# 1_1.net
KiCad netlist of a schematic drawn in EAGLE
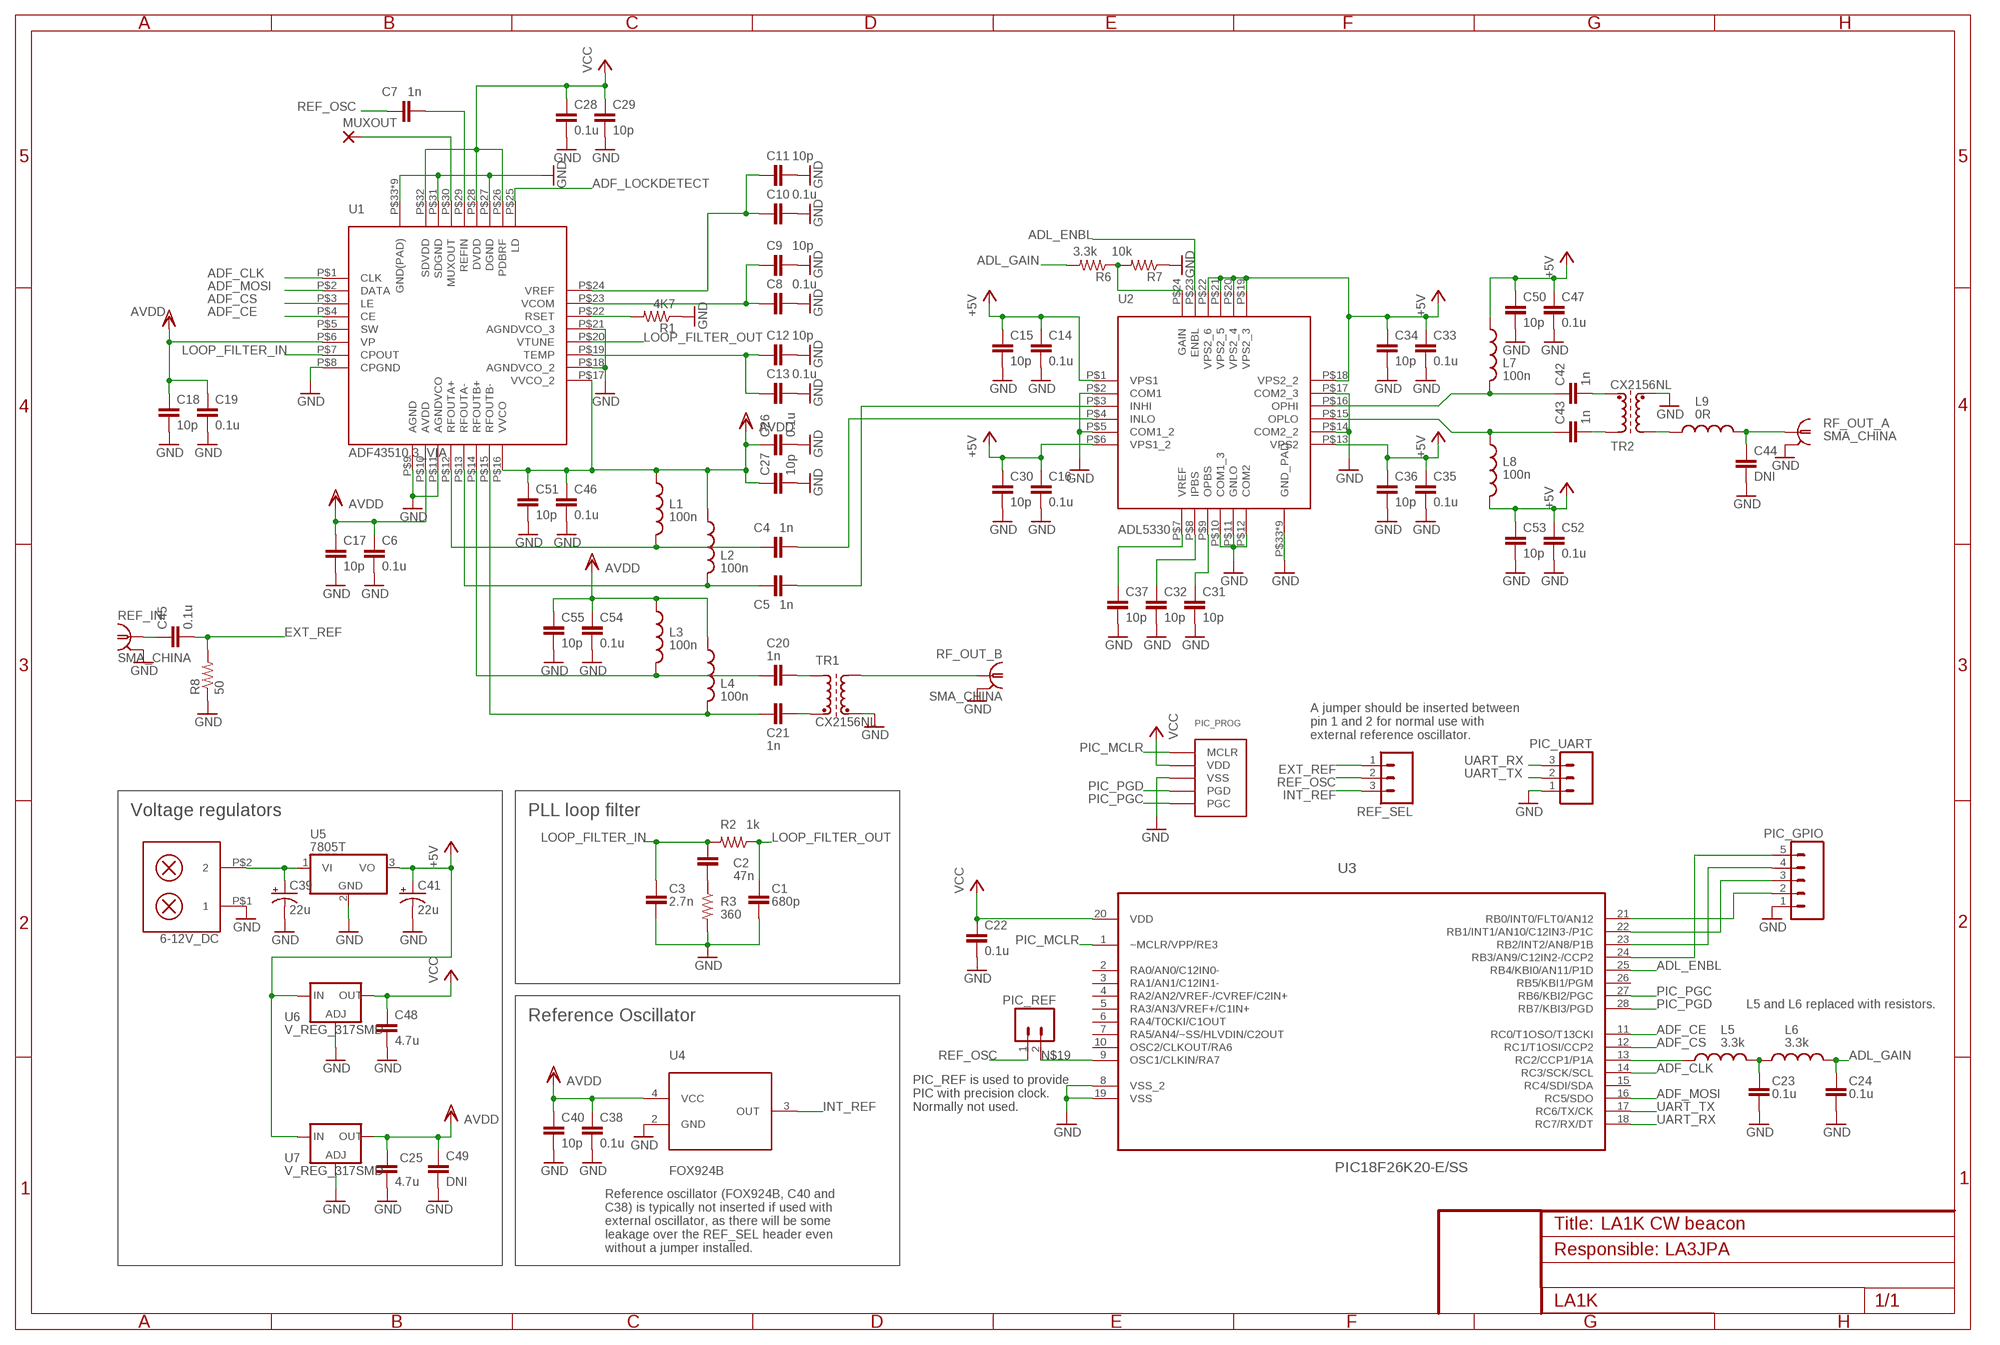
[diagram p0: schematic, sheet 1]

(export (version "E")
  (design (tool "Eeschema 10.0.6"))
  (components
    (comp (ref "6-12V_DC")
      (value "PK5602")
      (footprint "eagle-import:PK5602")
      (fields (field (name "PARTNO") "1984617"))
      (libsource (lib "eagle-import") (part "PK5602"))
    )
    (comp (ref "C1")
      (value "680p")
      (footprint "eagle-import:0603-CAP")
      (fields (field (name "PARTNO") "GRM1885C1H681JA01D"))
      (libsource (lib "eagle-import") (part "CAP0603-CAP"))
    )
    (comp (ref "C2")
      (value "47n")
      (footprint "eagle-import:0603-CAP")
      (fields (field (name "PARTNO") "GRM188R71E473JA01D"))
      (libsource (lib "eagle-import") (part "CAP0603-CAP"))
    )
    (comp (ref "C3")
      (value "2.7n")
      (footprint "eagle-import:0603-CAP")
      (fields (field (name "PARTNO") "GRM1885C1H272JA01D"))
      (libsource (lib "eagle-import") (part "CAP0603-CAP"))
    )
    (comp (ref "C4")
      (value "1n")
      (footprint "eagle-import:0603-CAP")
      (fields (field (name "PARTNO") "GRM1885C1H102FA01D"))
      (libsource (lib "eagle-import") (part "CAP0603-CAP"))
    )
    (comp (ref "C5")
      (value "1n")
      (footprint "eagle-import:0603-CAP")
      (fields (field (name "PARTNO") "GRM1885C1H102FA01D"))
      (libsource (lib "eagle-import") (part "CAP0603-CAP"))
    )
    (comp (ref "C6")
      (value "0.1u")
      (footprint "eagle-import:0603-CAP")
      (fields (field (name "PARTNO") "GRM188R71E104KA01D"))
      (libsource (lib "eagle-import") (part "CAP0603-CAP"))
    )
    (comp (ref "C7")
      (value "1n")
      (footprint "eagle-import:0603-CAP")
      (fields (field (name "PARTNO") "GRM1885C1H102FA01D"))
      (libsource (lib "eagle-import") (part "CAP0603-CAP"))
    )
    (comp (ref "C8")
      (value "0.1u")
      (footprint "eagle-import:0603-CAP")
      (fields (field (name "PARTNO") "GRM188R71E104KA01D"))
      (libsource (lib "eagle-import") (part "CAP0603-CAP"))
    )
    (comp (ref "C9")
      (value "10p")
      (footprint "eagle-import:0603-CAP")
      (fields (field (name "PARTNO") "GRM1885C1H100FA01D"))
      (libsource (lib "eagle-import") (part "CAP0603-CAP"))
    )
    (comp (ref "C10")
      (value "0.1u")
      (footprint "eagle-import:0603-CAP")
      (fields (field (name "PARTNO") "GRM188R71E104KA01D"))
      (libsource (lib "eagle-import") (part "CAP0603-CAP"))
    )
    (comp (ref "C11")
      (value "10p")
      (footprint "eagle-import:0603-CAP")
      (fields (field (name "PARTNO") "GRM1885C1H100FA01D"))
      (libsource (lib "eagle-import") (part "CAP0603-CAP"))
    )
    (comp (ref "C12")
      (value "10p")
      (footprint "eagle-import:0603-CAP")
      (fields (field (name "PARTNO") "GRM1885C1H100FA01D"))
      (libsource (lib "eagle-import") (part "CAP0603-CAP"))
    )
    (comp (ref "C13")
      (value "0.1u")
      (footprint "eagle-import:0603-CAP")
      (fields (field (name "PARTNO") "GRM188R71E104KA01D"))
      (libsource (lib "eagle-import") (part "CAP0603-CAP"))
    )
    (comp (ref "C14")
      (value "0.1u")
      (footprint "eagle-import:0603-CAP")
      (fields (field (name "PARTNO") "GRM188R71E104KA01D"))
      (libsource (lib "eagle-import") (part "CAP0603-CAP"))
    )
    (comp (ref "C15")
      (value "10p")
      (footprint "eagle-import:0603-CAP")
      (fields (field (name "PARTNO") "GRM1885C1H100FA01D"))
      (libsource (lib "eagle-import") (part "CAP0603-CAP"))
    )
    (comp (ref "C16")
      (value "0.1u")
      (footprint "eagle-import:0603-CAP")
      (fields (field (name "PARTNO") "GRM188R71E104KA01D"))
      (libsource (lib "eagle-import") (part "CAP0603-CAP"))
    )
    (comp (ref "C17")
      (value "10p")
      (footprint "eagle-import:0603-CAP")
      (fields (field (name "PARTNO") "GRM1885C1H100FA01D"))
      (libsource (lib "eagle-import") (part "CAP0603-CAP"))
    )
    (comp (ref "C18")
      (value "10p")
      (footprint "eagle-import:0603-CAP")
      (fields (field (name "PARTNO") "GRM1885C1H100FA01D"))
      (libsource (lib "eagle-import") (part "CAP0603-CAP"))
    )
    (comp (ref "C19")
      (value "0.1u")
      (footprint "eagle-import:0603-CAP")
      (fields (field (name "PARTNO") "GRM188R71E104KA01D"))
      (libsource (lib "eagle-import") (part "CAP0603-CAP"))
    )
    (comp (ref "C20")
      (value "1n")
      (footprint "eagle-import:0603-CAP")
      (fields (field (name "PARTNO") "GRM1885C1H102FA01D"))
      (libsource (lib "eagle-import") (part "CAP0603-CAP"))
    )
    (comp (ref "C21")
      (value "1n")
      (footprint "eagle-import:0603-CAP")
      (fields (field (name "PARTNO") "GRM1885C1H102FA01D"))
      (libsource (lib "eagle-import") (part "CAP0603-CAP"))
    )
    (comp (ref "C22")
      (value "0.1u")
      (footprint "eagle-import:0603-CAP")
      (fields (field (name "PARTNO") "GRM188R71E104KA01D"))
      (libsource (lib "eagle-import") (part "CAP0603-CAP"))
    )
    (comp (ref "C23")
      (value "0.1u")
      (footprint "eagle-import:0603-CAP")
      (fields (field (name "PARTNO") "GRM188R71E104KA01D"))
      (libsource (lib "eagle-import") (part "CAP0603-CAP"))
    )
    (comp (ref "C24")
      (value "0.1u")
      (footprint "eagle-import:0603-CAP")
      (fields (field (name "PARTNO") "GRM188R71E104KA01D"))
      (libsource (lib "eagle-import") (part "CAP0603-CAP"))
    )
    (comp (ref "C25")
      (value "4.7u")
      (footprint "eagle-import:C0805")
      (fields (field (name "PARTNO") "GRM21BR61E475KA12K"))
      (libsource (lib "eagle-import") (part "C-EUC0805"))
    )
    (comp (ref "C26")
      (value "0.1u")
      (footprint "eagle-import:0603-CAP")
      (fields (field (name "PARTNO") "GRM188R71E104KA01D"))
      (libsource (lib "eagle-import") (part "CAP0603-CAP"))
    )
    (comp (ref "C27")
      (value "10p")
      (footprint "eagle-import:0603-CAP")
      (fields (field (name "PARTNO") "GRM1885C1H100FA01D"))
      (libsource (lib "eagle-import") (part "CAP0603-CAP"))
    )
    (comp (ref "C28")
      (value "0.1u")
      (footprint "eagle-import:0603-CAP")
      (fields (field (name "PARTNO") "GRM188R71E104KA01D"))
      (libsource (lib "eagle-import") (part "CAP0603-CAP"))
    )
    (comp (ref "C29")
      (value "10p")
      (footprint "eagle-import:0603-CAP")
      (fields (field (name "PARTNO") "GRM1885C1H100FA01D"))
      (libsource (lib "eagle-import") (part "CAP0603-CAP"))
    )
    (comp (ref "C30")
      (value "10p")
      (footprint "eagle-import:0603-CAP")
      (fields (field (name "PARTNO") "GRM1885C1H100FA01D"))
      (libsource (lib "eagle-import") (part "CAP0603-CAP"))
    )
    (comp (ref "C31")
      (value "10p")
      (footprint "eagle-import:0603-CAP")
      (fields (field (name "PARTNO") "GRM1885C1H100FA01D"))
      (libsource (lib "eagle-import") (part "CAP0603-CAP"))
    )
    (comp (ref "C32")
      (value "10p")
      (footprint "eagle-import:0603-CAP")
      (fields (field (name "PARTNO") "GRM1885C1H100FA01D"))
      (libsource (lib "eagle-import") (part "CAP0603-CAP"))
    )
    (comp (ref "C33")
      (value "0.1u")
      (footprint "eagle-import:0603-CAP")
      (fields (field (name "PARTNO") "GRM188R71E104KA01D"))
      (libsource (lib "eagle-import") (part "CAP0603-CAP"))
    )
    (comp (ref "C34")
      (value "10p")
      (footprint "eagle-import:0603-CAP")
      (fields (field (name "PARTNO") "GRM1885C1H100FA01D"))
      (libsource (lib "eagle-import") (part "CAP0603-CAP"))
    )
    (comp (ref "C35")
      (value "0.1u")
      (footprint "eagle-import:0603-CAP")
      (fields (field (name "PARTNO") "GRM188R71E104KA01D"))
      (libsource (lib "eagle-import") (part "CAP0603-CAP"))
    )
    (comp (ref "C36")
      (value "10p")
      (footprint "eagle-import:0603-CAP")
      (fields (field (name "PARTNO") "GRM1885C1H100FA01D"))
      (libsource (lib "eagle-import") (part "CAP0603-CAP"))
    )
    (comp (ref "C37")
      (value "10p")
      (footprint "eagle-import:0603-CAP")
      (fields (field (name "PARTNO") "GRM1885C1H100FA01D"))
      (libsource (lib "eagle-import") (part "CAP0603-CAP"))
    )
    (comp (ref "C38")
      (value "0.1u")
      (footprint "eagle-import:0603-CAP")
      (fields (field (name "PARTNO") "GRM188R71E104KA01D"))
      (libsource (lib "eagle-import") (part "CAP0603-CAP"))
    )
    (comp (ref "C39")
      (value "22u")
      (footprint "eagle-import:VISHAY_C")
      (fields (field (name "PARTNO") "TH4C226K016C1400"))
      (libsource (lib "eagle-import") (part "CAP_POLSMD"))
    )
    (comp (ref "C40")
      (value "10p")
      (footprint "eagle-import:0603-CAP")
      (fields (field (name "PARTNO") "GRM1885C1H100FA01D"))
      (libsource (lib "eagle-import") (part "CAP0603-CAP"))
    )
    (comp (ref "C41")
      (value "22u")
      (footprint "eagle-import:VISHAY_C")
      (fields (field (name "PARTNO") "TH4C226K016C1400"))
      (libsource (lib "eagle-import") (part "CAP_POLSMD"))
    )
    (comp (ref "C42")
      (value "1n")
      (footprint "eagle-import:C0805K")
      (fields (field (name "PARTNO") "GRM1885C1H102FA01D"))
      (libsource (lib "eagle-import") (part "CAP"))
    )
    (comp (ref "C43")
      (value "1n")
      (footprint "eagle-import:C0805K")
      (fields (field (name "PARTNO") "GRM1885C1H102FA01D"))
      (libsource (lib "eagle-import") (part "CAP"))
    )
    (comp (ref "C44")
      (value "DNI")
      (footprint "eagle-import:C0805K")
      (libsource (lib "eagle-import") (part "CAP"))
    )
    (comp (ref "C45")
      (value "0.1u")
      (footprint "eagle-import:0603-CAP")
      (fields (field (name "PARTNO") "GRM188R71E104KA01D"))
      (libsource (lib "eagle-import") (part "CAP0603-CAP"))
    )
    (comp (ref "C46")
      (value "0.1u")
      (footprint "eagle-import:0603-CAP")
      (fields (field (name "PARTNO") "GRM188R71E104KA01D"))
      (libsource (lib "eagle-import") (part "CAP0603-CAP"))
    )
    (comp (ref "C47")
      (value "0.1u")
      (footprint "eagle-import:0603-CAP")
      (fields (field (name "PARTNO") "GRM188R71E104KA01D"))
      (libsource (lib "eagle-import") (part "CAP0603-CAP"))
    )
    (comp (ref "C48")
      (value "4.7u")
      (footprint "eagle-import:C0805")
      (fields (field (name "PARTNO") "GRM21BR61E475KA12K"))
      (libsource (lib "eagle-import") (part "C-EUC0805"))
    )
    (comp (ref "C49")
      (value "DNI")
      (footprint "eagle-import:C0805")
      (libsource (lib "eagle-import") (part "C-EUC0805"))
    )
    (comp (ref "C50")
      (value "10p")
      (footprint "eagle-import:0603-CAP")
      (fields (field (name "PARTNO") "GRM1885C1H100FA01D"))
      (libsource (lib "eagle-import") (part "CAP0603-CAP"))
    )
    (comp (ref "C51")
      (value "10p")
      (footprint "eagle-import:0603-CAP")
      (fields (field (name "PARTNO") "GRM1885C1H100FA01D"))
      (libsource (lib "eagle-import") (part "CAP0603-CAP"))
    )
    (comp (ref "C52")
      (value "0.1u")
      (footprint "eagle-import:0603-CAP")
      (fields (field (name "PARTNO") "GRM188R71E104KA01D"))
      (libsource (lib "eagle-import") (part "CAP0603-CAP"))
    )
    (comp (ref "C53")
      (value "10p")
      (footprint "eagle-import:0603-CAP")
      (fields (field (name "PARTNO") "GRM1885C1H100FA01D"))
      (libsource (lib "eagle-import") (part "CAP0603-CAP"))
    )
    (comp (ref "C54")
      (value "0.1u")
      (footprint "eagle-import:0603-CAP")
      (fields (field (name "PARTNO") "GRM188R71E104KA01D"))
      (libsource (lib "eagle-import") (part "CAP0603-CAP"))
    )
    (comp (ref "C55")
      (value "10p")
      (footprint "eagle-import:0603-CAP")
      (fields (field (name "PARTNO") "GRM1885C1H100FA01D"))
      (libsource (lib "eagle-import") (part "CAP0603-CAP"))
    )
    (comp (ref "L1")
      (value "100n")
      (footprint "eagle-import:0603")
      (fields (field (name "PARTNO") "LQW18ANR10J00D"))
      (libsource (lib "eagle-import") (part "INDUCTOR0603"))
    )
    (comp (ref "L2")
      (value "100n")
      (footprint "eagle-import:0603")
      (fields (field (name "PARTNO") "LQW18ANR10J00D"))
      (libsource (lib "eagle-import") (part "INDUCTOR0603"))
    )
    (comp (ref "L3")
      (value "100n")
      (footprint "eagle-import:0603")
      (fields (field (name "PARTNO") "LQW18ANR10J00D"))
      (libsource (lib "eagle-import") (part "INDUCTOR0603"))
    )
    (comp (ref "L4")
      (value "100n")
      (footprint "eagle-import:0603")
      (fields (field (name "PARTNO") "LQW18ANR10J00D"))
      (libsource (lib "eagle-import") (part "INDUCTOR0603"))
    )
    (comp (ref "L5")
      (value "3.3k")
      (footprint "eagle-import:0603")
      (fields (field (name "PARTNO") "MCR03ERTF3321"))
      (libsource (lib "eagle-import") (part "INDUCTOR0603"))
    )
    (comp (ref "L6")
      (value "3.3k")
      (footprint "eagle-import:0603")
      (fields (field (name "PARTNO") "MCR03ERTF3321"))
      (libsource (lib "eagle-import") (part "INDUCTOR0603"))
    )
    (comp (ref "L7")
      (value "100n")
      (footprint "eagle-import:C0805K")
      (fields (field (name "PARTNO") "LQW18ANR10J00D"))
      (libsource (lib "eagle-import") (part "INDUCTOR"))
    )
    (comp (ref "L8")
      (value "100n")
      (footprint "eagle-import:C0805K")
      (fields (field (name "PARTNO") "LQW18ANR10J00D"))
      (libsource (lib "eagle-import") (part "INDUCTOR"))
    )
    (comp (ref "L9")
      (value "0R")
      (footprint "eagle-import:C0805K")
      (libsource (lib "eagle-import") (part "INDUCTOR"))
    )
    (comp (ref "MUXOUT")
      (value "SMD2")
      (footprint "eagle-import:SMD1,27-2,54")
      (libsource (lib "eagle-import") (part "SMD2"))
    )
    (comp (ref "PIC_GPIO")
      (value "M05PTH")
      (footprint "eagle-import:1X05")
      (libsource (lib "eagle-import") (part "M05PTH"))
    )
    (comp (ref "PIC_PROG")
      (value "1X5_ICSP")
      (footprint "eagle-import:1X5_2MM")
      (fields (field (name "PARTNO") "M22-2510505"))
      (libsource (lib "eagle-import") (part "1X5_ICSP"))
    )
    (comp (ref "PIC_REF")
      (value "M02PTH")
      (footprint "eagle-import:1X02")
      (libsource (lib "eagle-import") (part "M02PTH"))
    )
    (comp (ref "PIC_UART")
      (value "M03PTH")
      (footprint "eagle-import:1X03")
      (libsource (lib "eagle-import") (part "M03PTH"))
    )
    (comp (ref "R1")
      (value "4K7")
      (footprint "eagle-import:0603-RES")
      (fields (field (name "PARTNO") "MCR03ERTF4701"))
      (libsource (lib "eagle-import") (part "RESISTOR0603-RES"))
    )
    (comp (ref "R2")
      (value "1k")
      (footprint "eagle-import:0603-RES")
      (fields (field (name "PARTNO") "MCR03ERTF1001"))
      (libsource (lib "eagle-import") (part "RESISTOR0603-RES"))
    )
    (comp (ref "R3")
      (value "360")
      (footprint "eagle-import:0603-RES")
      (fields (field (name "PARTNO") "MCR03ERTF3600"))
      (libsource (lib "eagle-import") (part "RESISTOR0603-RES"))
    )
    (comp (ref "R6")
      (value "3.3k")
      (footprint "eagle-import:0603-RES")
      (fields (field (name "PARTNO") "MCR03ERTF3321"))
      (libsource (lib "eagle-import") (part "RESISTOR0603-RES"))
    )
    (comp (ref "R7")
      (value "10k")
      (footprint "eagle-import:0603-RES")
      (fields (field (name "PARTNO") "MCR03ERTF1002"))
      (libsource (lib "eagle-import") (part "RESISTOR0603-RES"))
    )
    (comp (ref "R8")
      (value "50")
      (footprint "eagle-import:C0805K")
      (fields (field (name "PARTNO") "ERJ-P06J510V"))
      (libsource (lib "eagle-import") (part "RESISTOR"))
    )
    (comp (ref "REF_IN")
      (value "SMA_CHINA")
      (footprint "eagle-import:SMA-EDGE")
      (fields (field (name "PARTNO") "SMA-J-P-H-ST-EM1"))
      (libsource (lib "eagle-import") (part "SMA_CHINA"))
    )
    (comp (ref "REF_SEL")
      (value "M03PTH")
      (footprint "eagle-import:1X03")
      (libsource (lib "eagle-import") (part "M03PTH"))
    )
    (comp (ref "RF_OUT_A")
      (value "SMA_CHINA")
      (footprint "eagle-import:SMA-EDGE")
      (fields (field (name "PARTNO") "SMA-J-P-H-ST-EM1"))
      (libsource (lib "eagle-import") (part "SMA_CHINA"))
    )
    (comp (ref "RF_OUT_B")
      (value "SMA_CHINA")
      (footprint "eagle-import:SMA-EDGE")
      (fields (field (name "PARTNO") "SMA-J-P-H-ST-EM1"))
      (libsource (lib "eagle-import") (part "SMA_CHINA"))
    )
    (comp (ref "TR1")
      (value "CX2156NL")
      (footprint "eagle-import:CX2156NL")
      (libsource (lib "eagle-import") (part "CX2156NL"))
    )
    (comp (ref "TR2")
      (value "CX2156NL")
      (footprint "eagle-import:CX2156NL")
      (libsource (lib "eagle-import") (part "CX2156NL"))
    )
    (comp (ref "U1")
      (value "ADF43510.3_VIA")
      (footprint "eagle-import:LFCSP_CP-32-2_.3VIA")
      (fields (field (name "PARTNO") "ADF4351BCPZ-RL7"))
      (libsource (lib "eagle-import") (part "ADF43510.3_VIA"))
    )
    (comp (ref "U2")
      (value "ADL5330")
      (footprint "eagle-import:LFCSP_CP-24-2_.3VIA")
      (fields (field (name "PARTNO") "ADL5330ACPZ-REEL7"))
      (libsource (lib "eagle-import") (part "ADL5330"))
    )
    (comp (ref "U3")
      (value "PIC18F26K20-E/SS")
      (footprint "eagle-import:SOP65P780X200-28N")
      (fields (field (name "PARTNO") "PIC18F26K22-I/SS"))
      (libsource (lib "eagle-import") (part "PIC18F26K20-E/SS"))
    )
    (comp (ref "U4")
      (value "FOX924B")
      (footprint "eagle-import:FOX924B")
      (libsource (lib "eagle-import") (part "FOX924B"))
    )
    (comp (ref "U5")
      (value "7805T")
      (footprint "eagle-import:TO220H")
      (fields (field (name "PARTNO") "LM7805CT"))
      (libsource (lib "eagle-import") (part "78T05"))
    )
    (comp (ref "U6")
      (value "V_REG_317SMD")
      (footprint "eagle-import:SOT223")
      (fields (field (name "PARTNO") "AP2114H-3.3TRG1"))
      (libsource (lib "eagle-import") (part "V_REG_317SMD"))
    )
    (comp (ref "U7")
      (value "V_REG_317SMD")
      (footprint "eagle-import:SOT223")
      (fields (field (name "PARTNO") "AP2114H-3.3TRG1"))
      (libsource (lib "eagle-import") (part "V_REG_317SMD"))
    )
  )
  (nets
    (net (code "1") (name "+5V") (class "Default")
      (node (ref "C14") (pin "1") (pinfunction "1_1") (pintype "passive"))
      (node (ref "C15") (pin "1") (pinfunction "1_1") (pintype "passive"))
      (node (ref "C16") (pin "1") (pinfunction "1_1") (pintype "passive"))
      (node (ref "C30") (pin "1") (pinfunction "1_1") (pintype "passive"))
      (node (ref "C33") (pin "1") (pinfunction "1_1") (pintype "passive"))
      (node (ref "C34") (pin "1") (pinfunction "1_1") (pintype "passive"))
      (node (ref "C35") (pin "1") (pinfunction "1_1") (pintype "passive"))
      (node (ref "C36") (pin "1") (pinfunction "1_1") (pintype "passive"))
      (node (ref "C41") (pin "+") (pinfunction "+_+") (pintype "passive"))
      (node (ref "C47") (pin "1") (pinfunction "1_1") (pintype "passive"))
      (node (ref "C50") (pin "1") (pinfunction "1_1") (pintype "passive"))
      (node (ref "C52") (pin "1") (pinfunction "1_1") (pintype "passive"))
      (node (ref "C53") (pin "1") (pinfunction "1_1") (pintype "passive"))
      (node (ref "L7") (pin "1") (pinfunction "1_1") (pintype "passive"))
      (node (ref "L8") (pin "1") (pinfunction "1_1") (pintype "passive"))
      (node (ref "U2") (pin "P$1") (pinfunction "VPS1_P$1") (pintype "bidirectional"))
      (node (ref "U2") (pin "P$13") (pinfunction "VPS2_P$13") (pintype "bidirectional"))
      (node (ref "U2") (pin "P$18") (pinfunction "VPS2_2_P$18") (pintype "bidirectional"))
      (node (ref "U2") (pin "P$19") (pinfunction "VPS2_3_P$19") (pintype "bidirectional"))
      (node (ref "U2") (pin "P$20") (pinfunction "VPS2_4_P$20") (pintype "bidirectional"))
      (node (ref "U2") (pin "P$21") (pinfunction "VPS2_5_P$21") (pintype "bidirectional"))
      (node (ref "U2") (pin "P$22") (pinfunction "VPS2_6_P$22") (pintype "bidirectional"))
      (node (ref "U2") (pin "P$6") (pinfunction "VPS1_2_P$6") (pintype "bidirectional"))
      (node (ref "U5") (pin "3") (pinfunction "VO_3") (pintype "passive"))
      (node (ref "U6") (pin "3") (pinfunction "IN_3") (pintype "input"))
      (node (ref "U7") (pin "3") (pinfunction "IN_3") (pintype "input"))
    )
    (net (code "2") (name "/ADF_CE") (class "Default")
      (node (ref "U1") (pin "P$4") (pinfunction "CE_P$4") (pintype "bidirectional"))
      (node (ref "U3") (pin "11") (pinfunction "RC0/T1OSO/T13CKI_11") (pintype "bidirectional"))
    )
    (net (code "3") (name "/ADF_CLK") (class "Default")
      (node (ref "U1") (pin "P$1") (pinfunction "CLK_P$1") (pintype "bidirectional"))
      (node (ref "U3") (pin "14") (pinfunction "RC3/SCK/SCL_14") (pintype "bidirectional"))
    )
    (net (code "4") (name "/ADF_CS") (class "Default")
      (node (ref "U1") (pin "P$3") (pinfunction "LE_P$3") (pintype "bidirectional"))
      (node (ref "U3") (pin "12") (pinfunction "RC1/T1OSI/CCP2_12") (pintype "bidirectional"))
    )
    (net (code "5") (name "/ADF_LOCKDETECT") (class "Default")
      (node (ref "U1") (pin "P$25") (pinfunction "LD_P$25") (pintype "bidirectional"))
    )
    (net (code "6") (name "/ADF_MOSI") (class "Default")
      (node (ref "U1") (pin "P$2") (pinfunction "DATA_P$2") (pintype "bidirectional"))
      (node (ref "U3") (pin "16") (pinfunction "RC5/SDO_16") (pintype "bidirectional"))
    )
    (net (code "7") (name "/ADL_ENBL") (class "Default")
      (node (ref "U2") (pin "P$23") (pinfunction "ENBL_P$23") (pintype "bidirectional"))
      (node (ref "U3") (pin "25") (pinfunction "RB4/KBI0/AN11/P1D_25") (pintype "bidirectional"))
    )
    (net (code "8") (name "/ADL_GAIN") (class "Default")
      (node (ref "C24") (pin "2") (pinfunction "2_2") (pintype "passive"))
      (node (ref "L6") (pin "2") (pinfunction "2_2") (pintype "passive"))
      (node (ref "R6") (pin "2") (pinfunction "2_2") (pintype "passive"))
    )
    (net (code "9") (name "/EXT_REF") (class "Default")
      (node (ref "C45") (pin "2") (pinfunction "2_2") (pintype "passive"))
      (node (ref "R8") (pin "2") (pinfunction "2_2") (pintype "passive"))
      (node (ref "REF_SEL") (pin "1") (pinfunction "1_1") (pintype "passive"))
    )
    (net (code "10") (name "/INT_REF") (class "Default")
      (node (ref "REF_SEL") (pin "3") (pinfunction "3_3") (pintype "passive"))
      (node (ref "U4") (pin "3") (pinfunction "OUT_3") (pintype "bidirectional"))
    )
    (net (code "11") (name "/LOOP_FILTER_IN") (class "Default")
      (node (ref "C2") (pin "1") (pinfunction "1_1") (pintype "passive"))
      (node (ref "C3") (pin "1") (pinfunction "1_1") (pintype "passive"))
      (node (ref "R2") (pin "2") (pinfunction "2_2") (pintype "passive"))
      (node (ref "U1") (pin "P$7") (pinfunction "CPOUT_P$7") (pintype "bidirectional"))
    )
    (net (code "12") (name "/LOOP_FILTER_OUT") (class "Default")
      (node (ref "C1") (pin "1") (pinfunction "1_1") (pintype "passive"))
      (node (ref "R2") (pin "1") (pinfunction "1_1") (pintype "passive"))
      (node (ref "U1") (pin "P$20") (pinfunction "VTUNE_P$20") (pintype "bidirectional"))
    )
    (net (code "13") (name "/N$19") (class "Default")
      (node (ref "PIC_REF") (pin "2") (pinfunction "2_2") (pintype "passive"))
      (node (ref "U3") (pin "9") (pinfunction "OSC1/CLKIN/RA7_9") (pintype "bidirectional"))
    )
    (net (code "14") (name "/PIC_MCLR") (class "Default")
      (node (ref "PIC_PROG") (pin "P$1") (pinfunction "MCLR_P$1") (pintype "bidirectional"))
      (node (ref "U3") (pin "1") (pinfunction "~{MCLR/VPP/RE3}_1") (pintype "input"))
    )
    (net (code "15") (name "/PIC_PGC") (class "Default")
      (node (ref "PIC_PROG") (pin "P$5") (pinfunction "PGC_P$5") (pintype "bidirectional"))
      (node (ref "U3") (pin "27") (pinfunction "RB6/KBI2/PGC_27") (pintype "bidirectional"))
    )
    (net (code "16") (name "/PIC_PGD") (class "Default")
      (node (ref "PIC_PROG") (pin "P$4") (pinfunction "PGD_P$4") (pintype "bidirectional"))
      (node (ref "U3") (pin "28") (pinfunction "RB7/KBI3/PGD_28") (pintype "bidirectional"))
    )
    (net (code "17") (name "/REF_OSC") (class "Default")
      (node (ref "C7") (pin "1") (pinfunction "1_1") (pintype "passive"))
      (node (ref "PIC_REF") (pin "1") (pinfunction "1_1") (pintype "passive"))
      (node (ref "REF_SEL") (pin "2") (pinfunction "2_2") (pintype "passive"))
    )
    (net (code "18") (name "/UART_RX") (class "Default")
      (node (ref "PIC_UART") (pin "3") (pinfunction "3_3") (pintype "passive"))
      (node (ref "U3") (pin "18") (pinfunction "RC7/RX/DT_18") (pintype "bidirectional"))
    )
    (net (code "19") (name "/UART_TX") (class "Default")
      (node (ref "PIC_UART") (pin "2") (pinfunction "2_2") (pintype "passive"))
      (node (ref "U3") (pin "17") (pinfunction "RC6/TX/CK_17") (pintype "bidirectional"))
    )
    (net (code "20") (name "AVDD") (class "Default")
      (node (ref "C17") (pin "1") (pinfunction "1_1") (pintype "passive"))
      (node (ref "C18") (pin "1") (pinfunction "1_1") (pintype "passive"))
      (node (ref "C19") (pin "1") (pinfunction "1_1") (pintype "passive"))
      (node (ref "C25") (pin "1") (pinfunction "1_1") (pintype "passive"))
      (node (ref "C26") (pin "1") (pinfunction "1_1") (pintype "passive"))
      (node (ref "C27") (pin "1") (pinfunction "1_1") (pintype "passive"))
      (node (ref "C38") (pin "1") (pinfunction "1_1") (pintype "passive"))
      (node (ref "C40") (pin "1") (pinfunction "1_1") (pintype "passive"))
      (node (ref "C46") (pin "1") (pinfunction "1_1") (pintype "passive"))
      (node (ref "C49") (pin "1") (pinfunction "1_1") (pintype "passive"))
      (node (ref "C51") (pin "1") (pinfunction "1_1") (pintype "passive"))
      (node (ref "C54") (pin "1") (pinfunction "1_1") (pintype "passive"))
      (node (ref "C55") (pin "1") (pinfunction "1_1") (pintype "passive"))
      (node (ref "C6") (pin "1") (pinfunction "1_1") (pintype "passive"))
      (node (ref "L1") (pin "1") (pinfunction "1_1") (pintype "passive"))
      (node (ref "L2") (pin "1") (pinfunction "1_1") (pintype "passive"))
      (node (ref "L3") (pin "1") (pinfunction "1_1") (pintype "passive"))
      (node (ref "L4") (pin "1") (pinfunction "1_1") (pintype "passive"))
      (node (ref "U1") (pin "P$10") (pinfunction "AVDD_P$10") (pintype "bidirectional"))
      (node (ref "U1") (pin "P$16") (pinfunction "VVCO_P$16") (pintype "bidirectional"))
      (node (ref "U1") (pin "P$17") (pinfunction "VVCO_2_P$17") (pintype "bidirectional"))
      (node (ref "U1") (pin "P$6") (pinfunction "VP_P$6") (pintype "bidirectional"))
      (node (ref "U4") (pin "4") (pinfunction "VCC_4") (pintype "bidirectional"))
      (node (ref "U7") (pin "2") (pinfunction "OUT_2") (pintype "output"))
    )
    (net (code "21") (name "GND") (class "Default")
      (node (ref "6-12V_DC") (pin "P$1") (pinfunction "1_P$1") (pintype "bidirectional"))
      (node (ref "C1") (pin "2") (pinfunction "2_2") (pintype "passive"))
      (node (ref "C10") (pin "2") (pinfunction "2_2") (pintype "passive"))
      (node (ref "C11") (pin "2") (pinfunction "2_2") (pintype "passive"))
      (node (ref "C12") (pin "2") (pinfunction "2_2") (pintype "passive"))
      (node (ref "C13") (pin "2") (pinfunction "2_2") (pintype "passive"))
      (node (ref "C14") (pin "2") (pinfunction "2_2") (pintype "passive"))
      (node (ref "C15") (pin "2") (pinfunction "2_2") (pintype "passive"))
      (node (ref "C16") (pin "2") (pinfunction "2_2") (pintype "passive"))
      (node (ref "C17") (pin "2") (pinfunction "2_2") (pintype "passive"))
      (node (ref "C18") (pin "2") (pinfunction "2_2") (pintype "passive"))
      (node (ref "C19") (pin "2") (pinfunction "2_2") (pintype "passive"))
      (node (ref "C22") (pin "2") (pinfunction "2_2") (pintype "passive"))
      (node (ref "C23") (pin "1") (pinfunction "1_1") (pintype "passive"))
      (node (ref "C24") (pin "1") (pinfunction "1_1") (pintype "passive"))
      (node (ref "C25") (pin "2") (pinfunction "2_2") (pintype "passive"))
      (node (ref "C26") (pin "2") (pinfunction "2_2") (pintype "passive"))
      (node (ref "C27") (pin "2") (pinfunction "2_2") (pintype "passive"))
      (node (ref "C28") (pin "2") (pinfunction "2_2") (pintype "passive"))
      (node (ref "C29") (pin "2") (pinfunction "2_2") (pintype "passive"))
      (node (ref "C3") (pin "2") (pinfunction "2_2") (pintype "passive"))
      (node (ref "C30") (pin "2") (pinfunction "2_2") (pintype "passive"))
      (node (ref "C31") (pin "2") (pinfunction "2_2") (pintype "passive"))
      (node (ref "C32") (pin "2") (pinfunction "2_2") (pintype "passive"))
      (node (ref "C33") (pin "2") (pinfunction "2_2") (pintype "passive"))
      (node (ref "C34") (pin "2") (pinfunction "2_2") (pintype "passive"))
      (node (ref "C35") (pin "2") (pinfunction "2_2") (pintype "passive"))
      (node (ref "C36") (pin "2") (pinfunction "2_2") (pintype "passive"))
      (node (ref "C37") (pin "2") (pinfunction "2_2") (pintype "passive"))
      (node (ref "C38") (pin "2") (pinfunction "2_2") (pintype "passive"))
      (node (ref "C39") (pin "-") (pinfunction "-_-") (pintype "passive"))
      (node (ref "C40") (pin "2") (pinfunction "2_2") (pintype "passive"))
      (node (ref "C41") (pin "-") (pinfunction "-_-") (pintype "passive"))
      (node (ref "C44") (pin "2") (pinfunction "2_2") (pintype "passive"))
      (node (ref "C46") (pin "2") (pinfunction "2_2") (pintype "passive"))
      (node (ref "C47") (pin "2") (pinfunction "2_2") (pintype "passive"))
      (node (ref "C48") (pin "2") (pinfunction "2_2") (pintype "passive"))
      (node (ref "C49") (pin "2") (pinfunction "2_2") (pintype "passive"))
      (node (ref "C50") (pin "2") (pinfunction "2_2") (pintype "passive"))
      (node (ref "C51") (pin "2") (pinfunction "2_2") (pintype "passive"))
      (node (ref "C52") (pin "2") (pinfunction "2_2") (pintype "passive"))
      (node (ref "C53") (pin "2") (pinfunction "2_2") (pintype "passive"))
      (node (ref "C54") (pin "2") (pinfunction "2_2") (pintype "passive"))
      (node (ref "C55") (pin "2") (pinfunction "2_2") (pintype "passive"))
      (node (ref "C6") (pin "2") (pinfunction "2_2") (pintype "passive"))
      (node (ref "C8") (pin "2") (pinfunction "2_2") (pintype "passive"))
      (node (ref "C9") (pin "2") (pinfunction "2_2") (pintype "passive"))
      (node (ref "PIC_GPIO") (pin "1") (pinfunction "1_1") (pintype "passive"))
      (node (ref "PIC_PROG") (pin "P$3") (pinfunction "VSS_P$3") (pintype "power_in"))
      (node (ref "PIC_UART") (pin "1") (pinfunction "1_1") (pintype "passive"))
      (node (ref "R1") (pin "1") (pinfunction "1_1") (pintype "passive"))
      (node (ref "R3") (pin "2") (pinfunction "2_2") (pintype "passive"))
      (node (ref "R7") (pin "1") (pinfunction "1_1") (pintype "passive"))
      (node (ref "R8") (pin "1") (pinfunction "1_1") (pintype "passive"))
      (node (ref "REF_IN") (pin "GND@0") (pinfunction "GND_GND@0") (pintype "power_in"))
      (node (ref "REF_IN") (pin "GND@1") (pinfunction "GND_GND@1") (pintype "power_in"))
      (node (ref "REF_IN") (pin "GND@2") (pinfunction "GND_GND@2") (pintype "power_in"))
      (node (ref "REF_IN") (pin "GND@3") (pinfunction "GND_GND@3") (pintype "power_in"))
      (node (ref "RF_OUT_A") (pin "GND@0") (pinfunction "GND_GND@0") (pintype "power_in"))
      (node (ref "RF_OUT_A") (pin "GND@1") (pinfunction "GND_GND@1") (pintype "power_in"))
      (node (ref "RF_OUT_A") (pin "GND@2") (pinfunction "GND_GND@2") (pintype "power_in"))
      (node (ref "RF_OUT_A") (pin "GND@3") (pinfunction "GND_GND@3") (pintype "power_in"))
      (node (ref "RF_OUT_B") (pin "GND@0") (pinfunction "GND_GND@0") (pintype "power_in"))
      (node (ref "RF_OUT_B") (pin "GND@1") (pinfunction "GND_GND@1") (pintype "power_in"))
      (node (ref "RF_OUT_B") (pin "GND@2") (pinfunction "GND_GND@2") (pintype "power_in"))
      (node (ref "RF_OUT_B") (pin "GND@3") (pinfunction "GND_GND@3") (pintype "power_in"))
      (node (ref "TR1") (pin "5") (pinfunction "E2_5") (pintype "passive"))
      (node (ref "TR2") (pin "5") (pinfunction "E2_5") (pintype "passive"))
      (node (ref "U1") (pin "P$11") (pinfunction "AGNDVCO_P$11") (pintype "bidirectional"))
      (node (ref "U1") (pin "P$18") (pinfunction "AGNDVCO_2_P$18") (pintype "bidirectional"))
      (node (ref "U1") (pin "P$21") (pinfunction "AGNDVCO_3_P$21") (pintype "bidirectional"))
      (node (ref "U1") (pin "P$27") (pinfunction "DGND_P$27") (pintype "bidirectional"))
      (node (ref "U1") (pin "P$31") (pinfunction "SDGND_P$31") (pintype "bidirectional"))
      (node (ref "U1") (pin "P$33") (pinfunction "GND(PAD)_P$33") (pintype "bidirectional"))
      (node (ref "U1") (pin "P$34") (pinfunction "GND(PAD)_P$34") (pintype "bidirectional"))
      (node (ref "U1") (pin "P$35") (pinfunction "GND(PAD)_P$35") (pintype "bidirectional"))
      (node (ref "U1") (pin "P$36") (pinfunction "GND(PAD)_P$36") (pintype "bidirectional"))
      (node (ref "U1") (pin "P$37") (pinfunction "GND(PAD)_P$37") (pintype "bidirectional"))
      (node (ref "U1") (pin "P$38") (pinfunction "GND(PAD)_P$38") (pintype "bidirectional"))
      (node (ref "U1") (pin "P$39") (pinfunction "GND(PAD)_P$39") (pintype "bidirectional"))
      (node (ref "U1") (pin "P$40") (pinfunction "GND(PAD)_P$40") (pintype "bidirectional"))
      (node (ref "U1") (pin "P$41") (pinfunction "GND(PAD)_P$41") (pintype "bidirectional"))
      (node (ref "U1") (pin "P$8") (pinfunction "CPGND_P$8") (pintype "bidirectional"))
      (node (ref "U1") (pin "P$9") (pinfunction "AGND_P$9") (pintype "bidirectional"))
      (node (ref "U2") (pin "P$10") (pinfunction "COM1_3_P$10") (pintype "bidirectional"))
      (node (ref "U2") (pin "P$11") (pinfunction "GNLO_P$11") (pintype "bidirectional"))
      (node (ref "U2") (pin "P$12") (pinfunction "COM2_P$12") (pintype "bidirectional"))
      (node (ref "U2") (pin "P$14") (pinfunction "COM2_2_P$14") (pintype "bidirectional"))
      (node (ref "U2") (pin "P$17") (pinfunction "COM2_3_P$17") (pintype "bidirectional"))
      (node (ref "U2") (pin "P$2") (pinfunction "COM1_P$2") (pintype "bidirectional"))
      (node (ref "U2") (pin "P$33") (pinfunction "GND_PAD_P$33") (pintype "bidirectional"))
      (node (ref "U2") (pin "P$34") (pinfunction "GND_PAD_P$34") (pintype "bidirectional"))
      (node (ref "U2") (pin "P$35") (pinfunction "GND_PAD_P$35") (pintype "bidirectional"))
      (node (ref "U2") (pin "P$36") (pinfunction "GND_PAD_P$36") (pintype "bidirectional"))
      (node (ref "U2") (pin "P$37") (pinfunction "GND_PAD_P$37") (pintype "bidirectional"))
      (node (ref "U2") (pin "P$38") (pinfunction "GND_PAD_P$38") (pintype "bidirectional"))
      (node (ref "U2") (pin "P$39") (pinfunction "GND_PAD_P$39") (pintype "bidirectional"))
      (node (ref "U2") (pin "P$40") (pinfunction "GND_PAD_P$40") (pintype "bidirectional"))
      (node (ref "U2") (pin "P$41") (pinfunction "GND_PAD_P$41") (pintype "bidirectional"))
      (node (ref "U2") (pin "P$5") (pinfunction "COM1_2_P$5") (pintype "bidirectional"))
      (node (ref "U3") (pin "19") (pinfunction "VSS_19") (pintype "power_in"))
      (node (ref "U3") (pin "8") (pinfunction "VSS_2_8") (pintype "power_in"))
      (node (ref "U4") (pin "2") (pinfunction "GND_2") (pintype "bidirectional"))
      (node (ref "U5") (pin "2") (pinfunction "GND_2") (pintype "passive"))
      (node (ref "U6") (pin "1") (pinfunction "ADJ_1") (pintype "input"))
      (node (ref "U7") (pin "1") (pinfunction "ADJ_1") (pintype "input"))
    )
    (net (code "22") (name "Net-(6-12V_DC-2)") (class "Default")
      (node (ref "6-12V_DC") (pin "P$2") (pinfunction "2_P$2") (pintype "bidirectional"))
      (node (ref "C39") (pin "+") (pinfunction "+_+") (pintype "passive"))
      (node (ref "U5") (pin "1") (pinfunction "VI_1") (pintype "input"))
    )
    (net (code "23") (name "Net-(C2-Pad2)") (class "Default")
      (node (ref "C2") (pin "2") (pinfunction "2_2") (pintype "passive"))
      (node (ref "R3") (pin "1") (pinfunction "1_1") (pintype "passive"))
    )
    (net (code "24") (name "Net-(C23-Pad2)") (class "Default")
      (node (ref "C23") (pin "2") (pinfunction "2_2") (pintype "passive"))
      (node (ref "L5") (pin "2") (pinfunction "2_2") (pintype "passive"))
      (node (ref "L6") (pin "1") (pinfunction "1_1") (pintype "passive"))
    )
    (net (code "25") (name "Net-(MUXOUT-P)") (class "Default")
      (node (ref "MUXOUT") (pin "1") (pinfunction "P_1") (pintype "passive"))
      (node (ref "U1") (pin "P$30") (pinfunction "MUXOUT_P$30") (pintype "bidirectional"))
    )
    (net (code "26") (name "Net-(REF_IN-1)") (class "Default")
      (node (ref "C45") (pin "1") (pinfunction "1_1") (pintype "passive"))
      (node (ref "REF_IN") (pin "SIG") (pinfunction "1_SIG") (pintype "passive"))
    )
    (net (code "27") (name "Net-(RF_OUT_A-1)") (class "Default")
      (node (ref "C44") (pin "1") (pinfunction "1_1") (pintype "passive"))
      (node (ref "L9") (pin "2") (pinfunction "2_2") (pintype "passive"))
      (node (ref "RF_OUT_A") (pin "SIG") (pinfunction "1_SIG") (pintype "passive"))
    )
    (net (code "28") (name "Net-(RF_OUT_B-1)") (class "Default")
      (node (ref "RF_OUT_B") (pin "SIG") (pinfunction "1_SIG") (pintype "passive"))
      (node (ref "TR1") (pin "4") (pinfunction "A2_4") (pintype "passive"))
    )
    (net (code "29") (name "Net-(TR1-A1)") (class "Default")
      (node (ref "C20") (pin "2") (pinfunction "2_2") (pintype "passive"))
      (node (ref "TR1") (pin "3") (pinfunction "A1_3") (pintype "passive"))
    )
    (net (code "30") (name "Net-(TR1-E1)") (class "Default")
      (node (ref "C21") (pin "2") (pinfunction "2_2") (pintype "passive"))
      (node (ref "TR1") (pin "1") (pinfunction "E1_1") (pintype "passive"))
    )
    (net (code "31") (name "Net-(TR2-A1)") (class "Default")
      (node (ref "C43") (pin "2") (pinfunction "2_2") (pintype "passive"))
      (node (ref "TR2") (pin "3") (pinfunction "A1_3") (pintype "passive"))
    )
    (net (code "32") (name "Net-(TR2-A2)") (class "Default")
      (node (ref "L9") (pin "1") (pinfunction "1_1") (pintype "passive"))
      (node (ref "TR2") (pin "4") (pinfunction "A2_4") (pintype "passive"))
    )
    (net (code "33") (name "Net-(TR2-E1)") (class "Default")
      (node (ref "C42") (pin "2") (pinfunction "2_2") (pintype "passive"))
      (node (ref "TR2") (pin "1") (pinfunction "E1_1") (pintype "passive"))
    )
    (net (code "34") (name "Net-(U1-REFIN)") (class "Default")
      (node (ref "C7") (pin "2") (pinfunction "2_2") (pintype "passive"))
      (node (ref "U1") (pin "P$29") (pinfunction "REFIN_P$29") (pintype "bidirectional"))
    )
    (net (code "35") (name "Net-(U1-RFOUTA+)") (class "Default")
      (node (ref "C4") (pin "1") (pinfunction "1_1") (pintype "passive"))
      (node (ref "L1") (pin "2") (pinfunction "2_2") (pintype "passive"))
      (node (ref "U1") (pin "P$12") (pinfunction "RFOUTA+_P$12") (pintype "bidirectional"))
    )
    (net (code "36") (name "Net-(U1-RFOUTA-)") (class "Default")
      (node (ref "C5") (pin "1") (pinfunction "1_1") (pintype "passive"))
      (node (ref "L2") (pin "2") (pinfunction "2_2") (pintype "passive"))
      (node (ref "U1") (pin "P$13") (pinfunction "RFOUTA-_P$13") (pintype "bidirectional"))
    )
    (net (code "37") (name "Net-(U1-RFOUTB+)") (class "Default")
      (node (ref "C20") (pin "1") (pinfunction "1_1") (pintype "passive"))
      (node (ref "L3") (pin "2") (pinfunction "2_2") (pintype "passive"))
      (node (ref "U1") (pin "P$14") (pinfunction "RFOUTB+_P$14") (pintype "bidirectional"))
    )
    (net (code "38") (name "Net-(U1-RFOUTB-)") (class "Default")
      (node (ref "C21") (pin "1") (pinfunction "1_1") (pintype "passive"))
      (node (ref "L4") (pin "2") (pinfunction "2_2") (pintype "passive"))
      (node (ref "U1") (pin "P$15") (pinfunction "RFOUTB-_P$15") (pintype "bidirectional"))
    )
    (net (code "39") (name "Net-(U1-RSET)") (class "Default")
      (node (ref "R1") (pin "2") (pinfunction "2_2") (pintype "passive"))
      (node (ref "U1") (pin "P$22") (pinfunction "RSET_P$22") (pintype "bidirectional"))
    )
    (net (code "40") (name "Net-(U1-TEMP)") (class "Default")
      (node (ref "C12") (pin "1") (pinfunction "1_1") (pintype "passive"))
      (node (ref "C13") (pin "1") (pinfunction "1_1") (pintype "passive"))
      (node (ref "U1") (pin "P$19") (pinfunction "TEMP_P$19") (pintype "bidirectional"))
    )
    (net (code "41") (name "Net-(U1-VCOM)") (class "Default")
      (node (ref "C8") (pin "1") (pinfunction "1_1") (pintype "passive"))
      (node (ref "C9") (pin "1") (pinfunction "1_1") (pintype "passive"))
      (node (ref "U1") (pin "P$23") (pinfunction "VCOM_P$23") (pintype "bidirectional"))
    )
    (net (code "42") (name "Net-(U1-VREF)") (class "Default")
      (node (ref "C10") (pin "1") (pinfunction "1_1") (pintype "passive"))
      (node (ref "C11") (pin "1") (pinfunction "1_1") (pintype "passive"))
      (node (ref "U1") (pin "P$24") (pinfunction "VREF_P$24") (pintype "bidirectional"))
    )
    (net (code "43") (name "Net-(U2-GAIN)") (class "Default")
      (node (ref "R6") (pin "1") (pinfunction "1_1") (pintype "passive"))
      (node (ref "R7") (pin "2") (pinfunction "2_2") (pintype "passive"))
      (node (ref "U2") (pin "P$24") (pinfunction "GAIN_P$24") (pintype "bidirectional"))
    )
    (net (code "44") (name "Net-(U2-INHI)") (class "Default")
      (node (ref "C5") (pin "2") (pinfunction "2_2") (pintype "passive"))
      (node (ref "U2") (pin "P$3") (pinfunction "INHI_P$3") (pintype "bidirectional"))
    )
    (net (code "45") (name "Net-(U2-INLO)") (class "Default")
      (node (ref "C4") (pin "2") (pinfunction "2_2") (pintype "passive"))
      (node (ref "U2") (pin "P$4") (pinfunction "INLO_P$4") (pintype "bidirectional"))
    )
    (net (code "46") (name "Net-(U2-IPBS)") (class "Default")
      (node (ref "C32") (pin "1") (pinfunction "1_1") (pintype "passive"))
      (node (ref "U2") (pin "P$8") (pinfunction "IPBS_P$8") (pintype "bidirectional"))
    )
    (net (code "47") (name "Net-(U2-OPBS)") (class "Default")
      (node (ref "C31") (pin "1") (pinfunction "1_1") (pintype "passive"))
      (node (ref "U2") (pin "P$9") (pinfunction "OPBS_P$9") (pintype "bidirectional"))
    )
    (net (code "48") (name "Net-(U2-OPHI)") (class "Default")
      (node (ref "C42") (pin "1") (pinfunction "1_1") (pintype "passive"))
      (node (ref "L7") (pin "2") (pinfunction "2_2") (pintype "passive"))
      (node (ref "U2") (pin "P$16") (pinfunction "OPHI_P$16") (pintype "bidirectional"))
    )
    (net (code "49") (name "Net-(U2-OPLO)") (class "Default")
      (node (ref "C43") (pin "1") (pinfunction "1_1") (pintype "passive"))
      (node (ref "L8") (pin "2") (pinfunction "2_2") (pintype "passive"))
      (node (ref "U2") (pin "P$15") (pinfunction "OPLO_P$15") (pintype "bidirectional"))
    )
    (net (code "50") (name "Net-(U2-VREF)") (class "Default")
      (node (ref "C37") (pin "1") (pinfunction "1_1") (pintype "passive"))
      (node (ref "U2") (pin "P$7") (pinfunction "VREF_P$7") (pintype "bidirectional"))
    )
    (net (code "51") (name "Net-(U3-RB0{slash}INT0{slash}FLT0{slash}AN12)") (class "Default")
      (node (ref "PIC_GPIO") (pin "2") (pinfunction "2_2") (pintype "passive"))
      (node (ref "U3") (pin "21") (pinfunction "RB0/INT0/FLT0/AN12_21") (pintype "bidirectional"))
    )
    (net (code "52") (name "Net-(U3-RB1{slash}INT1{slash}AN10{slash}C12IN3-{slash}P1C)") (class "Default")
      (node (ref "PIC_GPIO") (pin "3") (pinfunction "3_3") (pintype "passive"))
      (node (ref "U3") (pin "22") (pinfunction "RB1/INT1/AN10/C12IN3-/P1C_22") (pintype "bidirectional"))
    )
    (net (code "53") (name "Net-(U3-RB2{slash}INT2{slash}AN8{slash}P1B)") (class "Default")
      (node (ref "PIC_GPIO") (pin "4") (pinfunction "4_4") (pintype "passive"))
      (node (ref "U3") (pin "23") (pinfunction "RB2/INT2/AN8/P1B_23") (pintype "bidirectional"))
    )
    (net (code "54") (name "Net-(U3-RB3{slash}AN9{slash}C12IN2-{slash}CCP2)") (class "Default")
      (node (ref "PIC_GPIO") (pin "5") (pinfunction "5_5") (pintype "passive"))
      (node (ref "U3") (pin "24") (pinfunction "RB3/AN9/C12IN2-/CCP2_24") (pintype "bidirectional"))
    )
    (net (code "55") (name "Net-(U3-RC2{slash}CCP1{slash}P1A)") (class "Default")
      (node (ref "L5") (pin "1") (pinfunction "1_1") (pintype "passive"))
      (node (ref "U3") (pin "13") (pinfunction "RC2/CCP1/P1A_13") (pintype "bidirectional"))
    )
    (net (code "56") (name "VCC") (class "Default")
      (node (ref "C22") (pin "1") (pinfunction "1_1") (pintype "passive"))
      (node (ref "C28") (pin "1") (pinfunction "1_1") (pintype "passive"))
      (node (ref "C29") (pin "1") (pinfunction "1_1") (pintype "passive"))
      (node (ref "C48") (pin "1") (pinfunction "1_1") (pintype "passive"))
      (node (ref "PIC_PROG") (pin "P$2") (pinfunction "VDD_P$2") (pintype "power_in"))
      (node (ref "U1") (pin "P$26") (pinfunction "PDBRF_P$26") (pintype "bidirectional"))
      (node (ref "U1") (pin "P$28") (pinfunction "DVDD_P$28") (pintype "bidirectional"))
      (node (ref "U1") (pin "P$32") (pinfunction "SDVDD_P$32") (pintype "bidirectional"))
      (node (ref "U3") (pin "20") (pinfunction "VDD_20") (pintype "power_in"))
      (node (ref "U6") (pin "2") (pinfunction "OUT_2") (pintype "output"))
    )
    (net (code "57") (name "unconnected-(U1-SW-PadP$5)") (class "Default")
      (node (ref "U1") (pin "P$5") (pinfunction "SW_P$5") (pintype "bidirectional"))
    )
    (net (code "58") (name "unconnected-(U3-OSC2{slash}CLKOUT{slash}RA6-Pad10)") (class "Default")
      (node (ref "U3") (pin "10") (pinfunction "OSC2/CLKOUT/RA6_10") (pintype "bidirectional"))
    )
    (net (code "59") (name "unconnected-(U3-RA0{slash}AN0{slash}C12IN0--Pad2)") (class "Default")
      (node (ref "U3") (pin "2") (pinfunction "RA0/AN0/C12IN0-_2") (pintype "bidirectional"))
    )
    (net (code "60") (name "unconnected-(U3-RA1{slash}AN1{slash}C12IN1--Pad3)") (class "Default")
      (node (ref "U3") (pin "3") (pinfunction "RA1/AN1/C12IN1-_3") (pintype "bidirectional"))
    )
    (net (code "61") (name "unconnected-(U3-RA2{slash}AN2{slash}VREF-{slash}CVREF{slash}C2IN+-Pad4)") (class "Default")
      (node (ref "U3") (pin "4") (pinfunction "RA2/AN2/VREF-/CVREF/C2IN+_4") (pintype "bidirectional"))
    )
    (net (code "62") (name "unconnected-(U3-RA3{slash}AN3{slash}VREF+{slash}C1IN+-Pad5)") (class "Default")
      (node (ref "U3") (pin "5") (pinfunction "RA3/AN3/VREF+/C1IN+_5") (pintype "bidirectional"))
    )
    (net (code "63") (name "unconnected-(U3-RA4{slash}T0CKI{slash}C1OUT-Pad6)") (class "Default")
      (node (ref "U3") (pin "6") (pinfunction "RA4/T0CKI/C1OUT_6") (pintype "bidirectional"))
    )
    (net (code "64") (name "unconnected-(U3-RA5{slash}AN4{slash}~{SS{slash}HLVDIN{slash}C2OUT}-Pad7)") (class "Default")
      (node (ref "U3") (pin "7") (pinfunction "RA5/AN4/~{SS/HLVDIN/C2OUT}_7") (pintype "bidirectional"))
    )
    (net (code "65") (name "unconnected-(U3-RB5{slash}KBI1{slash}PGM-Pad26)") (class "Default")
      (node (ref "U3") (pin "26") (pinfunction "RB5/KBI1/PGM_26") (pintype "bidirectional"))
    )
    (net (code "66") (name "unconnected-(U3-RC4{slash}SDI{slash}SDA-Pad15)") (class "Default")
      (node (ref "U3") (pin "15") (pinfunction "RC4/SDI/SDA_15") (pintype "bidirectional"))
    )
  )
)
